# SurfaceEEG_Central_V1_0.net
KiCad netlist of a schematic drawn in EAGLE
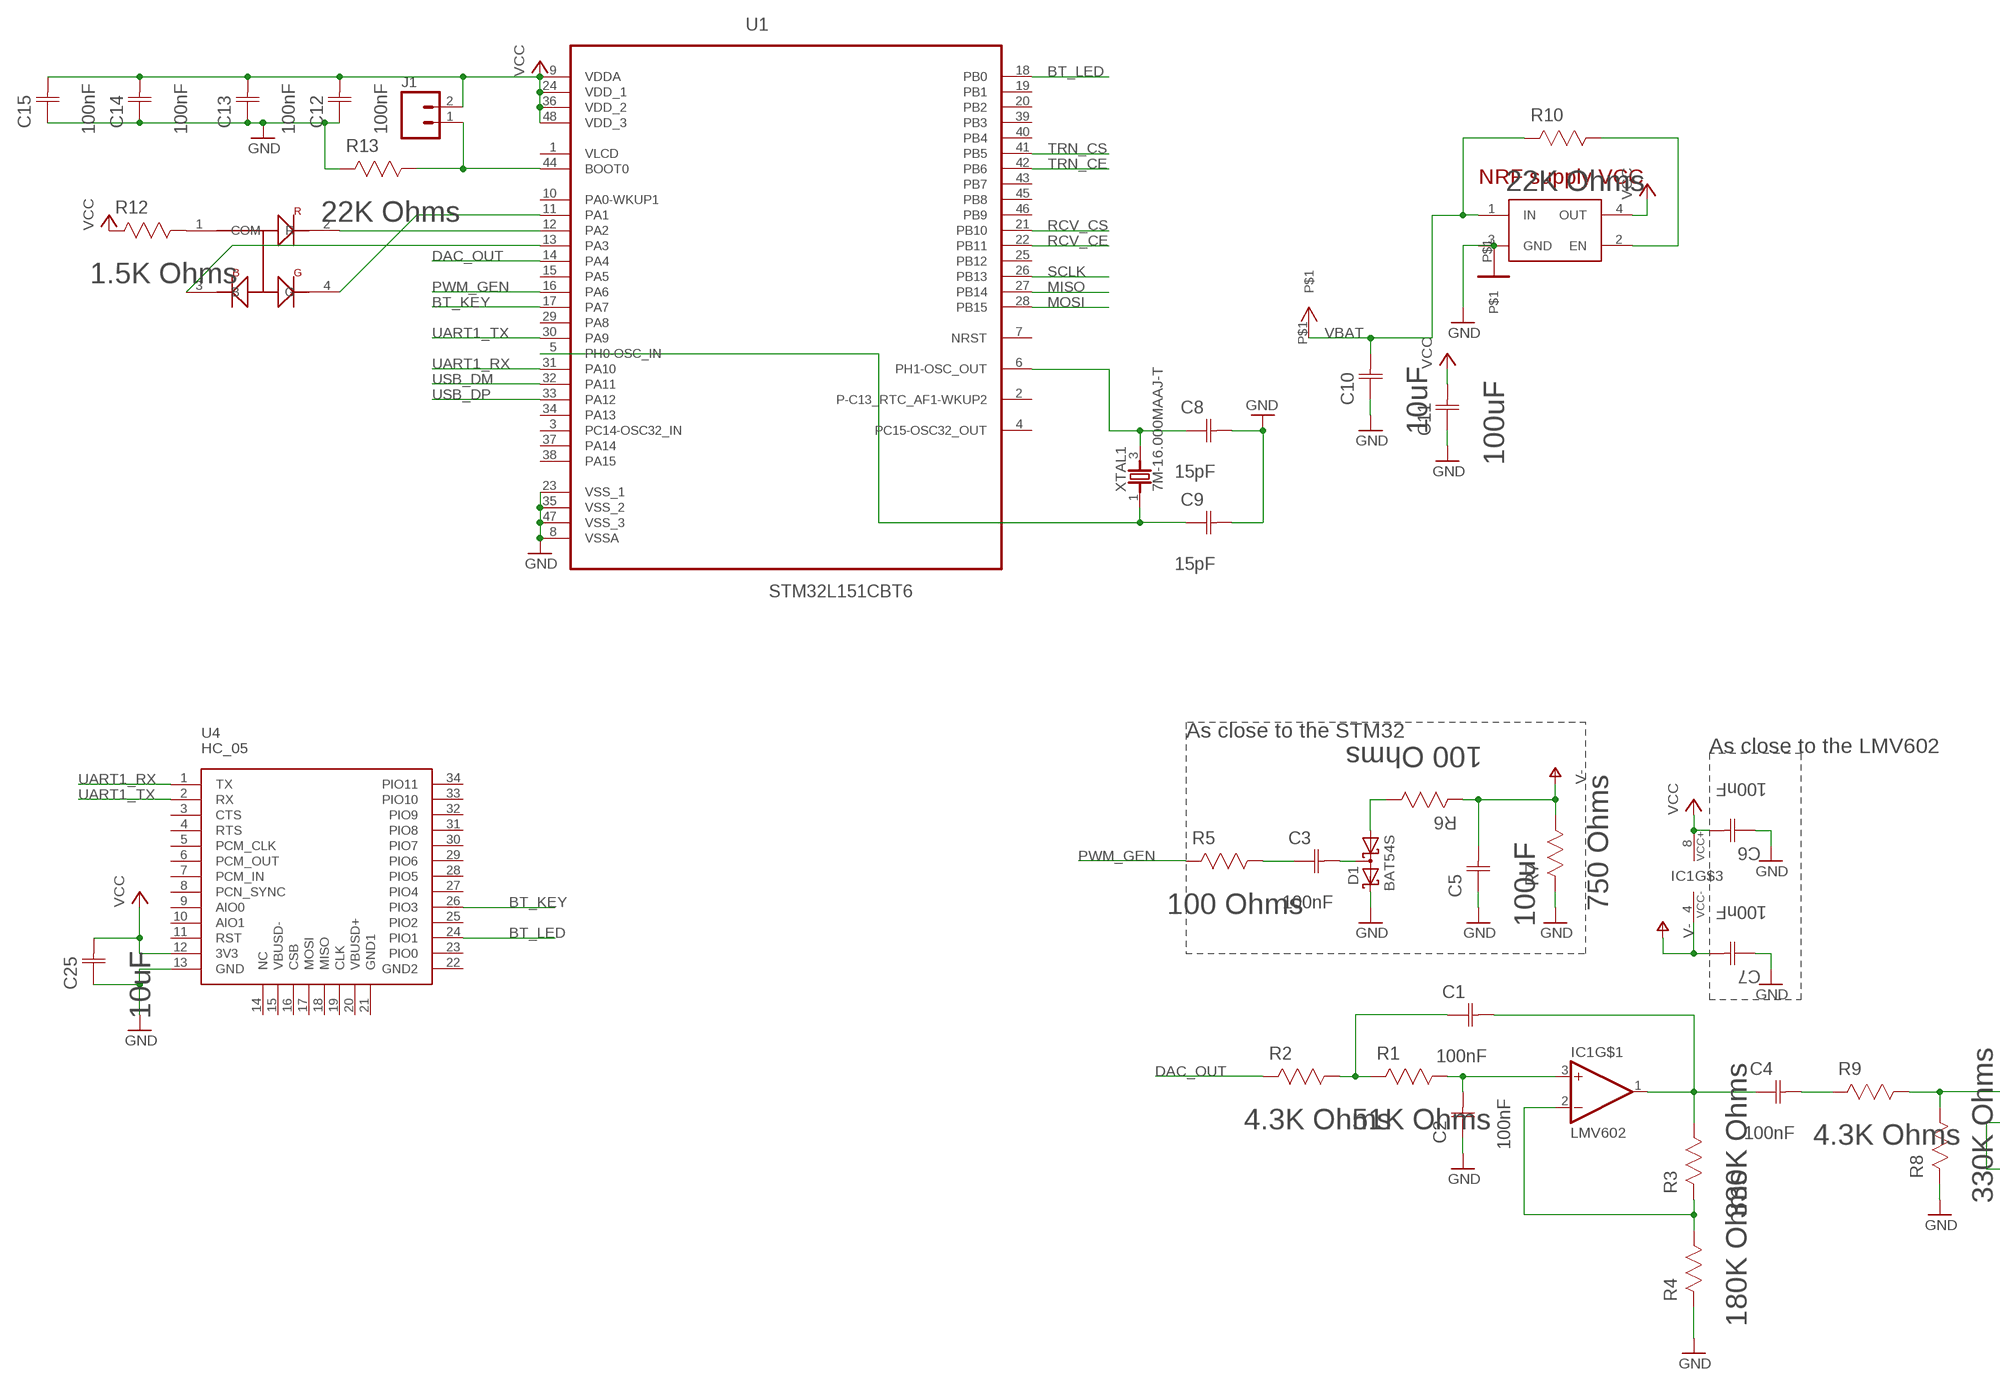
[diagram p0: schematic, sheet 1, part 1 of 2]
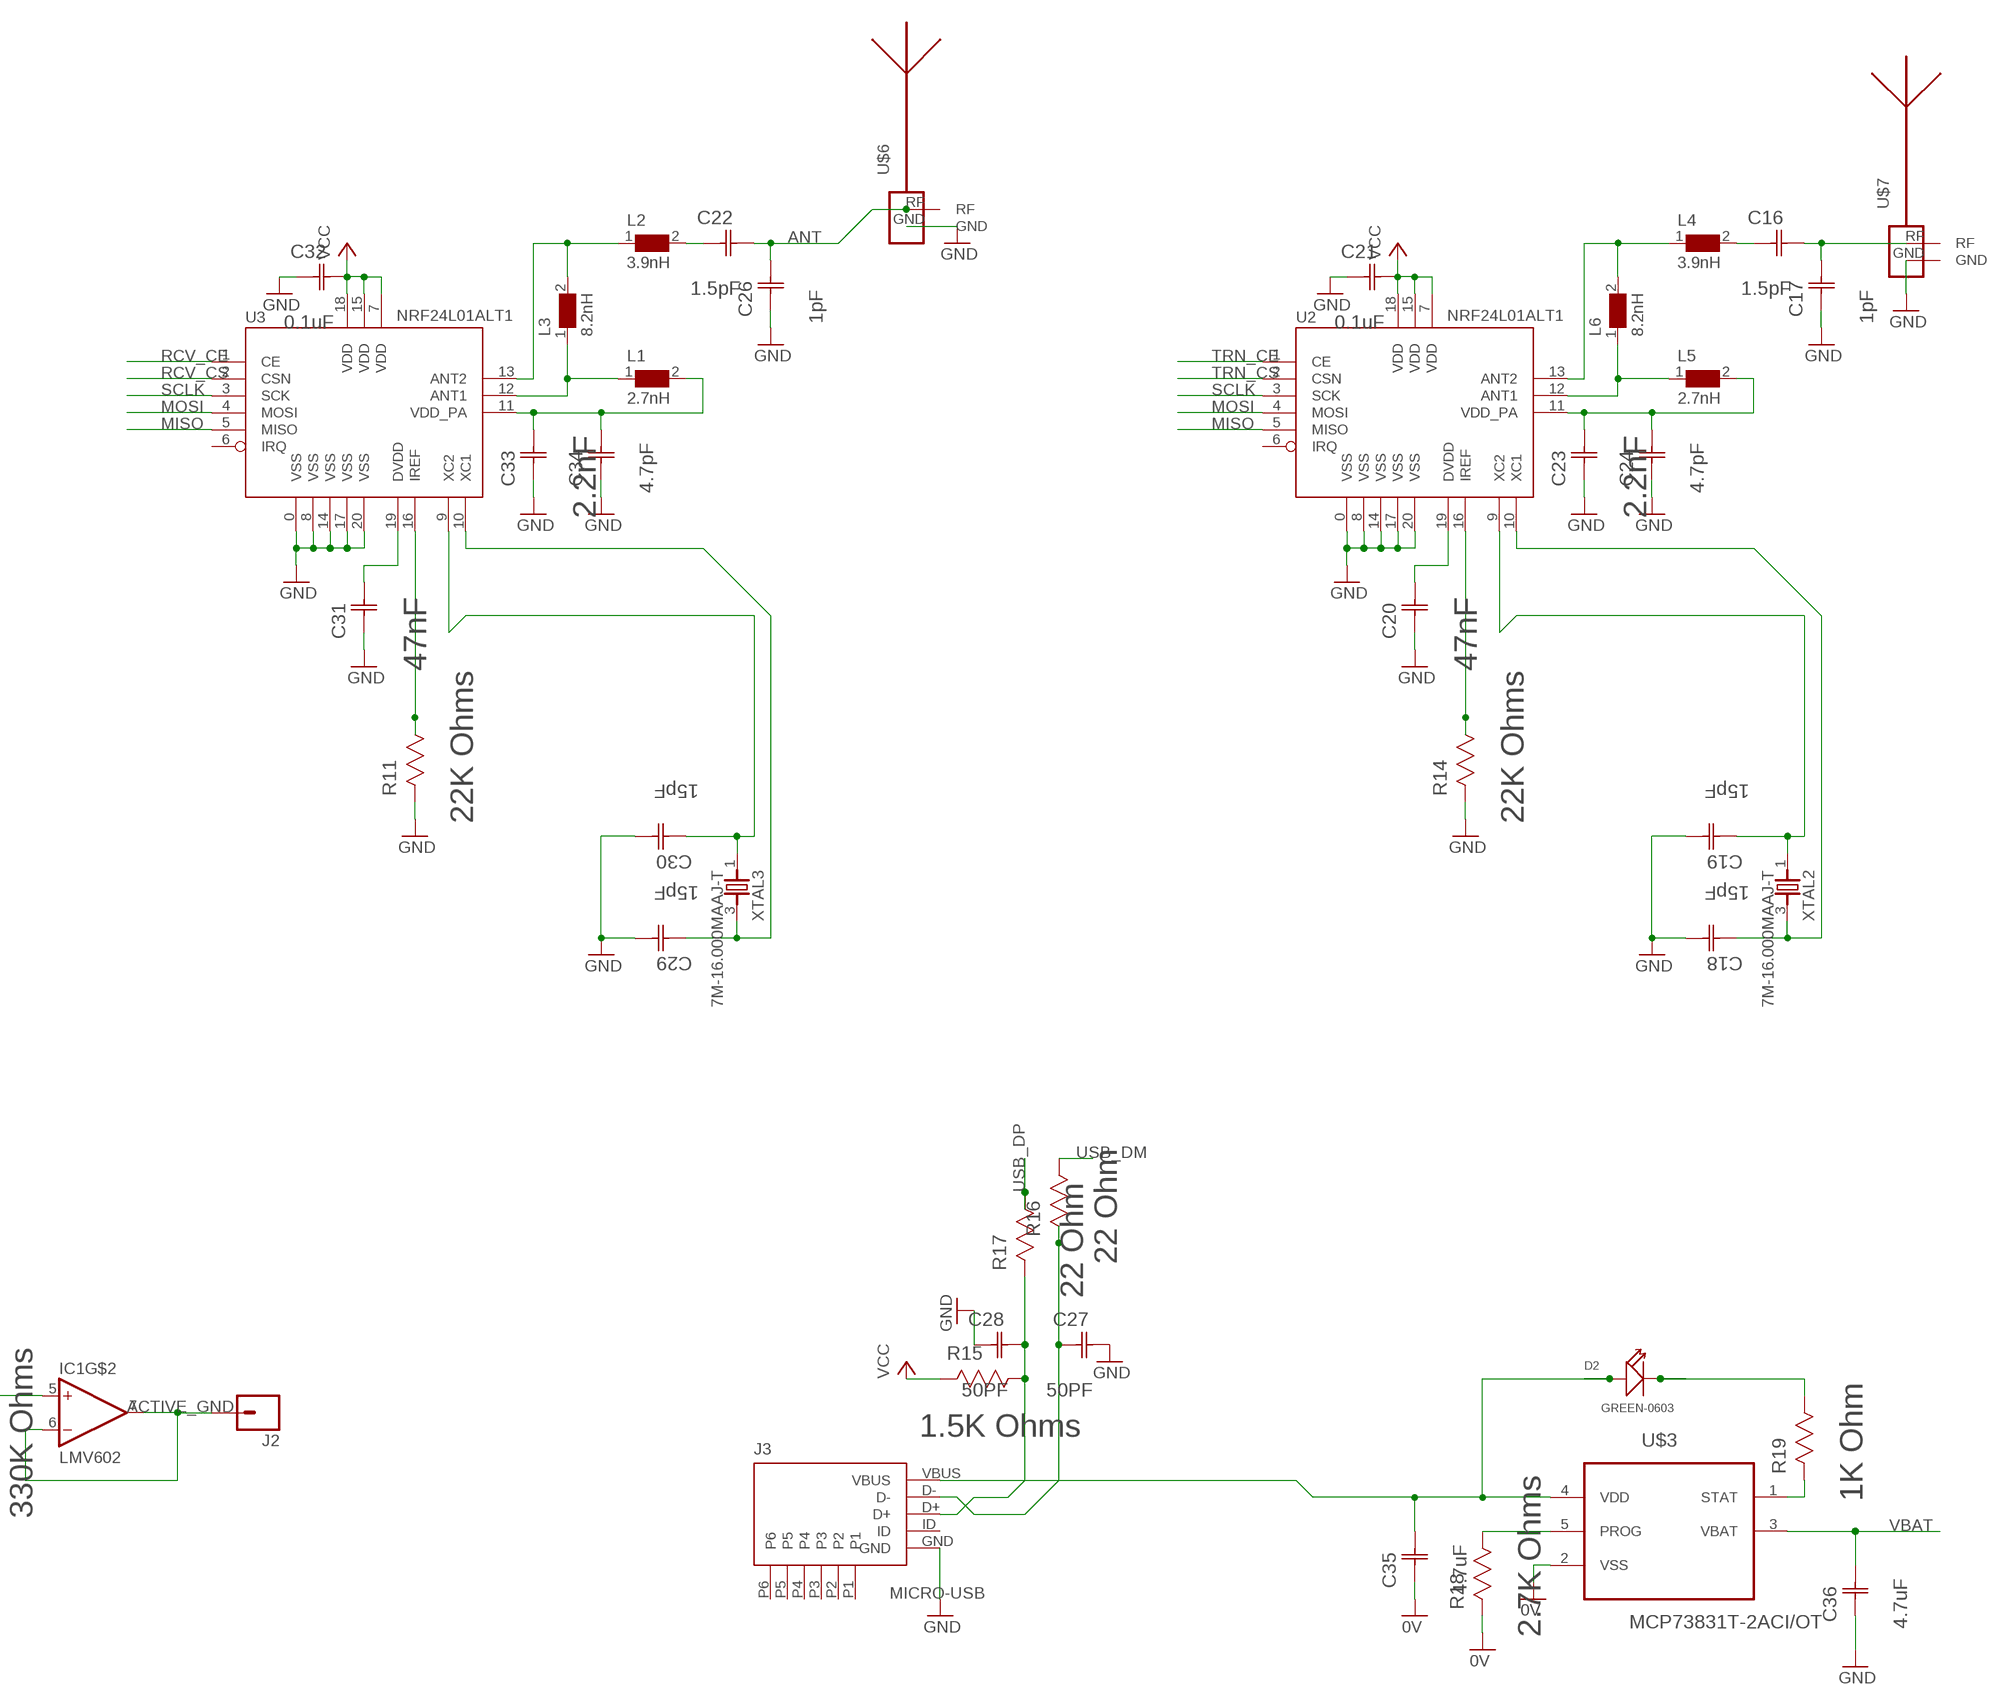
[diagram p1: schematic, sheet 1, part 2 of 2]

(export (version "E")
  (design (tool "Eeschema 10.0.6"))
  (components
    (comp (ref "C1")
      (value "100nF")
      (footprint "eagle-import:CAPC1608X90N")
      (fields (field (name "MPN") "06035C104KAT2A") (field (name "TOLERANCE") "±10%"))
      (libsource (lib "eagle-import") (part "06035C104KAT2A"))
    )
    (comp (ref "C2")
      (value "100nF")
      (footprint "eagle-import:CAPC1608X90N")
      (fields (field (name "MPN") "06035C104KAT2A") (field (name "TOLERANCE") "±10%"))
      (libsource (lib "eagle-import") (part "06035C104KAT2A"))
    )
    (comp (ref "C3")
      (value "100nF")
      (footprint "eagle-import:CAPC1608X90N")
      (fields (field (name "MPN") "06035C104KAT2A") (field (name "TOLERANCE") "±10%"))
      (libsource (lib "eagle-import") (part "06035C104KAT2A"))
    )
    (comp (ref "C4")
      (value "100nF")
      (footprint "eagle-import:CAPC1608X90N")
      (fields (field (name "MPN") "06035C104KAT2A") (field (name "TOLERANCE") "±10%"))
      (libsource (lib "eagle-import") (part "06035C104KAT2A"))
    )
    (comp (ref "C5")
      (value "100uF")
      (footprint "eagle-import:CAPC3216X180N")
      (fields (field (name "MPN") "C1206C107M9PACTU") (field (name "TOLERANCE") "±20%"))
      (libsource (lib "eagle-import") (part "C1206C107M9PACTU"))
    )
    (comp (ref "C6")
      (value "100nF")
      (footprint "eagle-import:CAPC1608X90N")
      (fields (field (name "MPN") "06035C104KAT2A") (field (name "TOLERANCE") "±10%"))
      (libsource (lib "eagle-import") (part "06035C104KAT2A"))
    )
    (comp (ref "C7")
      (value "100nF")
      (footprint "eagle-import:CAPC1608X90N")
      (fields (field (name "MPN") "06035C104KAT2A") (field (name "TOLERANCE") "±10%"))
      (libsource (lib "eagle-import") (part "06035C104KAT2A"))
    )
    (comp (ref "C8")
      (value "15pF")
      (footprint "eagle-import:CAPC1005X60N")
      (fields (field (name "MPN") "UQCL2A150JAT2A/500") (field (name "TOLERANCE") "±5%"))
      (libsource (lib "eagle-import") (part "UQCL2A150JAT2A/500"))
    )
    (comp (ref "C9")
      (value "15pF")
      (footprint "eagle-import:CAPC1005X60N")
      (fields (field (name "MPN") "UQCL2A150JAT2A/500") (field (name "TOLERANCE") "±5%"))
      (libsource (lib "eagle-import") (part "UQCL2A150JAT2A/500"))
    )
    (comp (ref "C10")
      (value "10uF")
      (footprint "eagle-import:CAPC1608X85N")
      (fields (field (name "MPN") "C0603C106M9PACTU") (field (name "TOLERANCE") "±20%"))
      (libsource (lib "eagle-import") (part "C0603C106M9PACTU"))
    )
    (comp (ref "C11")
      (value "100uF")
      (footprint "eagle-import:CAPC3216X180N")
      (fields (field (name "MPN") "C1206C107M9PACTU") (field (name "TOLERANCE") "±20%"))
      (libsource (lib "eagle-import") (part "C1206C107M9PACTU"))
    )
    (comp (ref "C12")
      (value "100nF")
      (footprint "eagle-import:CAPC1608X90N")
      (fields (field (name "MPN") "06035C104KAT2A") (field (name "TOLERANCE") "±10%"))
      (libsource (lib "eagle-import") (part "06035C104KAT2A"))
    )
    (comp (ref "C13")
      (value "100nF")
      (footprint "eagle-import:CAPC1608X90N")
      (fields (field (name "MPN") "06035C104KAT2A") (field (name "TOLERANCE") "±10%"))
      (libsource (lib "eagle-import") (part "06035C104KAT2A"))
    )
    (comp (ref "C14")
      (value "100nF")
      (footprint "eagle-import:CAPC1608X90N")
      (fields (field (name "MPN") "06035C104KAT2A") (field (name "TOLERANCE") "±10%"))
      (libsource (lib "eagle-import") (part "06035C104KAT2A"))
    )
    (comp (ref "C15")
      (value "100nF")
      (footprint "eagle-import:CAPC1608X90N")
      (fields (field (name "MPN") "06035C104KAT2A") (field (name "TOLERANCE") "±10%"))
      (libsource (lib "eagle-import") (part "06035C104KAT2A"))
    )
    (comp (ref "C16")
      (value "1.5pF")
      (footprint "eagle-import:CAPC1005X60N")
      (fields (field (name "MPN") "UQCL2A1R5BAT2A/500") (field (name "TOLERANCE") "±.1 pF"))
      (libsource (lib "eagle-import") (part "UQCL2A1R5BAT2A/500"))
    )
    (comp (ref "C17")
      (value "1pF")
      (footprint "eagle-import:CAPC1005X60N")
      (fields (field (name "MPN") "UQCL2A1R0BAT2A/500") (field (name "TOLERANCE") "±.1 pF"))
      (libsource (lib "eagle-import") (part "UQCL2A1R0BAT2A/500"))
    )
    (comp (ref "C18")
      (value "15pF")
      (footprint "eagle-import:CAPC1005X60N")
      (fields (field (name "MPN") "UQCL2A150JAT2A/500") (field (name "TOLERANCE") "±5%"))
      (libsource (lib "eagle-import") (part "UQCL2A150JAT2A/500"))
    )
    (comp (ref "C19")
      (value "15pF")
      (footprint "eagle-import:CAPC1005X60N")
      (fields (field (name "MPN") "UQCL2A150JAT2A/500") (field (name "TOLERANCE") "±5%"))
      (libsource (lib "eagle-import") (part "UQCL2A150JAT2A/500"))
    )
    (comp (ref "C20")
      (value "47nF")
      (footprint "eagle-import:CAPC1608X85N")
      (fields (field (name "MPN") "C0603C473K1RACTU") (field (name "TOLERANCE") "±10%"))
      (libsource (lib "eagle-import") (part "C0603C473K1RACTU"))
    )
    (comp (ref "C21")
      (value "0.1uF")
      (footprint "eagle-import:CAPC1005X60N")
      (fields (field (name "MPN") "04023C104KAT2A") (field (name "TOLERANCE") "±10%"))
      (libsource (lib "eagle-import") (part "04023C104KAT2A"))
    )
    (comp (ref "C22")
      (value "1.5pF")
      (footprint "eagle-import:CAPC1005X60N")
      (fields (field (name "MPN") "UQCL2A1R5BAT2A/500") (field (name "TOLERANCE") "±.1 pF"))
      (libsource (lib "eagle-import") (part "UQCL2A1R5BAT2A/500"))
    )
    (comp (ref "C23")
      (value "2.2nF")
      (footprint "eagle-import:CAPC1005X60N")
      (fields (field (name "MPN") "C0402C222K5RACTU") (field (name "TOLERANCE") "±10%"))
      (libsource (lib "eagle-import") (part "C0402C222K5RACTU"))
    )
    (comp (ref "C24")
      (value "4.7pF")
      (footprint "eagle-import:CAPC1005X60N")
      (fields (field (name "MPN") "UQCL2A4R7CAT2A/500") (field (name "TOLERANCE") "±.25 pF"))
      (libsource (lib "eagle-import") (part "UQCL2A4R7CAT2A/500"))
    )
    (comp (ref "C25")
      (value "10uF")
      (footprint "eagle-import:CAPC1608X85N")
      (fields (field (name "MPN") "C0603C106M9PACTU") (field (name "TOLERANCE") "±20%"))
      (libsource (lib "eagle-import") (part "C0603C106M9PACTU"))
    )
    (comp (ref "C26")
      (value "1pF")
      (footprint "eagle-import:CAPC1005X60N")
      (fields (field (name "MPN") "UQCL2A1R0BAT2A/500") (field (name "TOLERANCE") "±.1 pF"))
      (libsource (lib "eagle-import") (part "UQCL2A1R0BAT2A/500"))
    )
    (comp (ref "C27")
      (value "50PF")
      (footprint "eagle-import:CAPC1608X90N")
      (fields (field (name "MPN") "06035A500JAT2A") (field (name "TOLERANCE") "±5%"))
      (libsource (lib "eagle-import") (part "06035A500JAT2A"))
    )
    (comp (ref "C28")
      (value "50PF")
      (footprint "eagle-import:CAPC1608X90N")
      (fields (field (name "MPN") "06035A500JAT2A") (field (name "TOLERANCE") "±5%"))
      (libsource (lib "eagle-import") (part "06035A500JAT2A"))
    )
    (comp (ref "C29")
      (value "15pF")
      (footprint "eagle-import:CAPC1005X60N")
      (fields (field (name "MPN") "UQCL2A150JAT2A/500") (field (name "TOLERANCE") "±5%"))
      (libsource (lib "eagle-import") (part "UQCL2A150JAT2A/500"))
    )
    (comp (ref "C30")
      (value "15pF")
      (footprint "eagle-import:CAPC1005X60N")
      (fields (field (name "MPN") "UQCL2A150JAT2A/500") (field (name "TOLERANCE") "±5%"))
      (libsource (lib "eagle-import") (part "UQCL2A150JAT2A/500"))
    )
    (comp (ref "C31")
      (value "47nF")
      (footprint "eagle-import:CAPC1608X85N")
      (fields (field (name "MPN") "C0603C473K1RACTU") (field (name "TOLERANCE") "±10%"))
      (libsource (lib "eagle-import") (part "C0603C473K1RACTU"))
    )
    (comp (ref "C32")
      (value "0.1uF")
      (footprint "eagle-import:CAPC1005X60N")
      (fields (field (name "MPN") "04023C104KAT2A") (field (name "TOLERANCE") "±10%"))
      (libsource (lib "eagle-import") (part "04023C104KAT2A"))
    )
    (comp (ref "C33")
      (value "2.2nF")
      (footprint "eagle-import:CAPC1005X60N")
      (fields (field (name "MPN") "C0402C222K5RACTU") (field (name "TOLERANCE") "±10%"))
      (libsource (lib "eagle-import") (part "C0402C222K5RACTU"))
    )
    (comp (ref "C34")
      (value "4.7pF")
      (footprint "eagle-import:CAPC1005X60N")
      (fields (field (name "MPN") "UQCL2A4R7CAT2A/500") (field (name "TOLERANCE") "±.25 pF"))
      (libsource (lib "eagle-import") (part "UQCL2A4R7CAT2A/500"))
    )
    (comp (ref "C35")
      (value "4.7uF")
      (footprint "eagle-import:CAPC2013X152N")
      (fields (field (name "MPN") "0805YC475KAT2A") (field (name "TOLERANCE") "±10%"))
      (libsource (lib "eagle-import") (part "0805YC475KAT2A"))
    )
    (comp (ref "C36")
      (value "4.7uF")
      (footprint "eagle-import:CAPC2013X152N")
      (fields (field (name "MPN") "0805YC475KAT2A") (field (name "TOLERANCE") "±10%"))
      (libsource (lib "eagle-import") (part "0805YC475KAT2A"))
    )
    (comp (ref "D1")
      (value "BAT54S")
      (footprint "eagle-import:SOT23")
      (libsource (lib "eagle-import") (part "BAT54S"))
    )
    (comp (ref "D2")
      (value "GREEN-0603")
      (footprint "eagle-import:LED-0603")
      (fields (field (name "MPN") "19-217-G7C-AN1P2-3T"))
      (libsource (lib "eagle-import") (part "SMD-LED-CLEAR-GREEN(0603)"))
    )
    (comp (ref "IC1")
      (value "LMV602")
      (footprint "eagle-import:VSSOP8")
      (fields (field (name "MPN") "LMV602MM/NOPB"))
      (libsource (lib "eagle-import") (part "LMV602"))
    )
    (comp (ref "J1")
      (value "M02PTH")
      (footprint "eagle-import:1X02")
      (libsource (lib "eagle-import") (part "M02PTH"))
    )
    (comp (ref "J2")
      (value "M01SMD-4.5X1.5")
      (footprint "eagle-import:PAD-1.5X4.5")
      (libsource (lib "eagle-import") (part "M01SMD-4.5X1.5"))
    )
    (comp (ref "J3")
      (value "MICRO-USB")
      (footprint "eagle-import:MICRO_USB")
      (fields (field (name "MPN") "47346-0001") (field (name "PARTNO") "AS-ITM-00021"))
      (libsource (lib "eagle-import") (part "MICRO-USB"))
    )
    (comp (ref "L1")
      (value "2.7nH")
      (footprint "eagle-import:WE-KI_0402A")
      (fields (field (name "MPN") "744765027A"))
      (libsource (lib "eagle-import") (part "WE-KI_0402A-744765027A"))
    )
    (comp (ref "L2")
      (value "3.9nH")
      (footprint "eagle-import:WE-KI_0402A")
      (fields (field (name "MPN") "744765039A"))
      (libsource (lib "eagle-import") (part "WE-KI_0402A-744765039A"))
    )
    (comp (ref "L3")
      (value "8.2nH")
      (footprint "eagle-import:WE-KI_0402A")
      (fields (field (name "MPN") "744765082A"))
      (libsource (lib "eagle-import") (part "WE-KI_0402A-744765082A"))
    )
    (comp (ref "L4")
      (value "3.9nH")
      (footprint "eagle-import:WE-KI_0402A")
      (fields (field (name "MPN") "744765039A"))
      (libsource (lib "eagle-import") (part "WE-KI_0402A-744765039A"))
    )
    (comp (ref "L5")
      (value "2.7nH")
      (footprint "eagle-import:WE-KI_0402A")
      (fields (field (name "MPN") "744765027A"))
      (libsource (lib "eagle-import") (part "WE-KI_0402A-744765027A"))
    )
    (comp (ref "L6")
      (value "8.2nH")
      (footprint "eagle-import:WE-KI_0402A")
      (fields (field (name "MPN") "744765082A"))
      (libsource (lib "eagle-import") (part "WE-KI_0402A-744765082A"))
    )
    (comp (ref "R1")
      (value "51K Ohms")
      (footprint "eagle-import:RESC1608X60N")
      (fields (field (name "MPN") "RC0603FR-0751KL") (field (name "TOLERANCE") "±1%"))
      (libsource (lib "eagle-import") (part "RC0603FR-0751KL"))
    )
    (comp (ref "R2")
      (value "4.3K Ohms")
      (footprint "eagle-import:RESC1608X60N")
      (fields (field (name "MPN") "RC0603FR-074K3L") (field (name "TOLERANCE") "±1%"))
      (libsource (lib "eagle-import") (part "RC0603FR-074K3L"))
    )
    (comp (ref "R3")
      (value "330K Ohms")
      (footprint "eagle-import:RESC1608X60N")
      (fields (field (name "MPN") "RC0603JR-07330KL") (field (name "TOLERANCE") "±5%"))
      (libsource (lib "eagle-import") (part "RC0603JR-07330KL"))
    )
    (comp (ref "R4")
      (value "180K Ohms")
      (footprint "eagle-import:RESC1608X60N")
      (fields (field (name "MPN") "RC0603JR-07180KL") (field (name "TOLERANCE") "±5%"))
      (libsource (lib "eagle-import") (part "RC0603JR-07180KL"))
    )
    (comp (ref "R5")
      (value "100 Ohms")
      (footprint "eagle-import:RESC1608X60N")
      (fields (field (name "MPN") "RC0603FR-07100RL") (field (name "TOLERANCE") "±1%"))
      (libsource (lib "eagle-import") (part "RC0603FR-07100RL"))
    )
    (comp (ref "R6")
      (value "100 Ohms")
      (footprint "eagle-import:RESC1608X60N")
      (fields (field (name "MPN") "RC0603FR-07100RL") (field (name "TOLERANCE") "±1%"))
      (libsource (lib "eagle-import") (part "RC0603FR-07100RL"))
    )
    (comp (ref "R7")
      (value "750 Ohms")
      (footprint "eagle-import:RESC1608X60N")
      (fields (field (name "MPN") "RC0603FR-07750RL") (field (name "TOLERANCE") "±1%"))
      (libsource (lib "eagle-import") (part "RC0603FR-07750RL"))
    )
    (comp (ref "R8")
      (value "330K Ohms")
      (footprint "eagle-import:RESC1608X60N")
      (fields (field (name "MPN") "RC0603JR-07330KL") (field (name "TOLERANCE") "±5%"))
      (libsource (lib "eagle-import") (part "RC0603JR-07330KL"))
    )
    (comp (ref "R9")
      (value "4.3K Ohms")
      (footprint "eagle-import:RESC1608X60N")
      (fields (field (name "MPN") "RC0603FR-074K3L") (field (name "TOLERANCE") "±1%"))
      (libsource (lib "eagle-import") (part "RC0603FR-074K3L"))
    )
    (comp (ref "R10")
      (value "22K Ohms")
      (footprint "eagle-import:RESC1608X60N")
      (fields (field (name "MPN") "RC0603FR-0722KL") (field (name "TOLERANCE") "±1%"))
      (libsource (lib "eagle-import") (part "RC0603FR-0722KL"))
    )
    (comp (ref "R11")
      (value "22K Ohms")
      (footprint "eagle-import:RESC1608X60N")
      (fields (field (name "MPN") "RC0603FR-0722KL") (field (name "TOLERANCE") "±1%"))
      (libsource (lib "eagle-import") (part "RC0603FR-0722KL"))
    )
    (comp (ref "R12")
      (value "1.5K Ohms")
      (footprint "eagle-import:RESC1608X60N")
      (fields (field (name "MPN") "RC0603FR-071K5L") (field (name "TOLERANCE") "±1%"))
      (libsource (lib "eagle-import") (part "RC0603FR-071K5L"))
    )
    (comp (ref "R13")
      (value "22K Ohms")
      (footprint "eagle-import:RESC1608X60N")
      (fields (field (name "MPN") "RC0603FR-0722KL") (field (name "TOLERANCE") "±1%"))
      (libsource (lib "eagle-import") (part "RC0603FR-0722KL"))
    )
    (comp (ref "R14")
      (value "22K Ohms")
      (footprint "eagle-import:RESC1608X60N")
      (fields (field (name "MPN") "RC0603FR-0722KL") (field (name "TOLERANCE") "±1%"))
      (libsource (lib "eagle-import") (part "RC0603FR-0722KL"))
    )
    (comp (ref "R15")
      (value "1.5K Ohms")
      (footprint "eagle-import:RESC1608X60N")
      (fields (field (name "MPN") "RC0603FR-071K5L") (field (name "TOLERANCE") "±1%"))
      (libsource (lib "eagle-import") (part "RC0603FR-071K5L"))
    )
    (comp (ref "R16")
      (value "22 Ohm")
      (footprint "eagle-import:RESC1608X60N")
      (fields (field (name "MPN") "9C06031A22R0JLHFT") (field (name "TOLERANCE") "±5%"))
      (libsource (lib "eagle-import") (part "9C06031A22R0JLHFT"))
    )
    (comp (ref "R17")
      (value "22 Ohm")
      (footprint "eagle-import:RESC1608X60N")
      (fields (field (name "MPN") "9C06031A22R0JLHFT") (field (name "TOLERANCE") "±5%"))
      (libsource (lib "eagle-import") (part "9C06031A22R0JLHFT"))
    )
    (comp (ref "R18")
      (value "2.7K Ohms")
      (footprint "eagle-import:RESC1608X60N")
      (fields (field (name "MPN") "RC0603FR-072K7L") (field (name "TOLERANCE") "±1%"))
      (libsource (lib "eagle-import") (part "RC0603FR-072K7L"))
    )
    (comp (ref "R19")
      (value "1K Ohm")
      (footprint "eagle-import:RESC1608X60N")
      (fields (field (name "MPN") "9C06031A1001JLHFT") (field (name "TOLERANCE") "±5%"))
      (libsource (lib "eagle-import") (part "9C06031A1001JLHFT"))
    )
    (comp (ref "U$1")
      (value "NCP103")
      (footprint "eagle-import:UDFN4-1_1")
      (fields (field (name "MPN") "NCP103AMX330TCG"))
      (libsource (lib "eagle-import") (part "NCP103"))
    )
    (comp (ref "U$2")
      (value "RGB-LED")
      (footprint "eagle-import:1615-RGB-LED")
      (libsource (lib "eagle-import") (part "RGB-LED"))
    )
    (comp (ref "U$3")
      (value "MCP73831T-2ACI/OT")
      (footprint "eagle-import:SOT95P280X145-5N")
      (libsource (lib "eagle-import") (part "MCP73831T-2ACI/OT"))
    )
    (comp (ref "U$4")
      (value "VCC")
      (footprint "eagle-import:VCC-PAD")
      (libsource (lib "eagle-import") (part "VCC"))
    )
    (comp (ref "U$5")
      (value "GND")
      (footprint "eagle-import:GND-PAD")
      (libsource (lib "eagle-import") (part "GND"))
    )
    (comp (ref "U$6")
      (value "ANTENNA_1LEFT")
      (footprint "eagle-import:SWRA117D_LEFT")
      (libsource (lib "eagle-import") (part "ANTENNA_1LEFT"))
    )
    (comp (ref "U$7")
      (value "ANTENNA_1RIGHT")
      (footprint "eagle-import:SWRA117D_RIGHT")
      (libsource (lib "eagle-import") (part "ANTENNA_1RIGHT"))
    )
    (comp (ref "U1")
      (value "STM32L151CBT6")
      (footprint "eagle-import:QFP50P900X900X160-48N")
      (libsource (lib "eagle-import") (part "STM32L151CBT6"))
    )
    (comp (ref "U2")
      (value "NRF24L01ALT1")
      (footprint "eagle-import:QFN20_ALT1")
      (libsource (lib "eagle-import") (part "NRF24L01ALT1"))
    )
    (comp (ref "U3")
      (value "NRF24L01ALT1")
      (footprint "eagle-import:QFN20_ALT1")
      (libsource (lib "eagle-import") (part "NRF24L01ALT1"))
    )
    (comp (ref "U4")
      (value "HC_05")
      (footprint "eagle-import:BLUETOOTH_SMD")
      (libsource (lib "eagle-import") (part "HC_05"))
    )
    (comp (ref "XTAL1")
      (value "7M-16.000MAAJ-T")
      (footprint "eagle-import:TXC_7M-16.000MAAJ-T")
      (fields (field (name "MPN") "7M-16.000MAAJ-T "))
      (libsource (lib "eagle-import") (part "7M-16.000MAAJ-T"))
    )
    (comp (ref "XTAL2")
      (value "7M-16.000MAAJ-T")
      (footprint "eagle-import:TXC_7M-16.000MAAJ-T")
      (fields (field (name "MPN") "7M-16.000MAAJ-T "))
      (libsource (lib "eagle-import") (part "7M-16.000MAAJ-T"))
    )
    (comp (ref "XTAL3")
      (value "7M-16.000MAAJ-T")
      (footprint "eagle-import:TXC_7M-16.000MAAJ-T")
      (fields (field (name "MPN") "7M-16.000MAAJ-T "))
      (libsource (lib "eagle-import") (part "7M-16.000MAAJ-T"))
    )
  )
  (nets
    (net (code "1") (name "/ACTIVE_GND") (class "Default")
      (node (ref "IC1") (pin "6") (pinfunction "IN-_6") (pintype "input"))
      (node (ref "IC1") (pin "7") (pinfunction "OUT_7") (pintype "output"))
      (node (ref "J2") (pin "P$1") (pinfunction "1_P$1") (pintype "passive"))
    )
    (net (code "2") (name "/ANT") (class "Default")
      (node (ref "C22") (pin "1") (pinfunction "C2_1") (pintype "passive"))
      (node (ref "C26") (pin "1") (pinfunction "C2_1") (pintype "passive"))
      (node (ref "U$6") (pin "RF") (pinfunction "RF_RF") (pintype "bidirectional"))
    )
    (net (code "3") (name "/BT_KEY") (class "Default")
      (node (ref "U1") (pin "17") (pinfunction "PA7_17") (pintype "bidirectional"))
      (node (ref "U4") (pin "26") (pinfunction "PIO3_26") (pintype "bidirectional"))
    )
    (net (code "4") (name "/BT_LED") (class "Default")
      (node (ref "U1") (pin "18") (pinfunction "PB0_18") (pintype "bidirectional"))
      (node (ref "U4") (pin "24") (pinfunction "PIO1_24") (pintype "bidirectional"))
    )
    (net (code "5") (name "/DAC_OUT") (class "Default")
      (node (ref "R2") (pin "2") (pinfunction "R2_2") (pintype "passive"))
      (node (ref "U1") (pin "14") (pinfunction "PA4_14") (pintype "bidirectional"))
    )
    (net (code "6") (name "/MISO") (class "Default")
      (node (ref "U1") (pin "27") (pinfunction "PB14_27") (pintype "bidirectional"))
      (node (ref "U2") (pin "5") (pinfunction "MISO_5") (pintype "output"))
      (node (ref "U3") (pin "5") (pinfunction "MISO_5") (pintype "output"))
    )
    (net (code "7") (name "/MOSI") (class "Default")
      (node (ref "U1") (pin "28") (pinfunction "PB15_28") (pintype "bidirectional"))
      (node (ref "U2") (pin "4") (pinfunction "MOSI_4") (pintype "input"))
      (node (ref "U3") (pin "4") (pinfunction "MOSI_4") (pintype "input"))
    )
    (net (code "8") (name "/PWM_GEN") (class "Default")
      (node (ref "R5") (pin "2") (pinfunction "R2_2") (pintype "passive"))
      (node (ref "U1") (pin "16") (pinfunction "PA6_16") (pintype "bidirectional"))
    )
    (net (code "9") (name "/RCV_CE") (class "Default")
      (node (ref "U1") (pin "22") (pinfunction "PB11_22") (pintype "bidirectional"))
      (node (ref "U3") (pin "1") (pinfunction "CE_1") (pintype "input"))
    )
    (net (code "10") (name "/RCV_CS") (class "Default")
      (node (ref "U1") (pin "21") (pinfunction "PB10_21") (pintype "bidirectional"))
      (node (ref "U3") (pin "2") (pinfunction "CSN_2") (pintype "input"))
    )
    (net (code "11") (name "/SCLK") (class "Default")
      (node (ref "U1") (pin "26") (pinfunction "PB13_26") (pintype "bidirectional"))
      (node (ref "U2") (pin "3") (pinfunction "SCK_3") (pintype "input"))
      (node (ref "U3") (pin "3") (pinfunction "SCK_3") (pintype "input"))
    )
    (net (code "12") (name "/TRN_CE") (class "Default")
      (node (ref "U1") (pin "42") (pinfunction "PB6_42") (pintype "bidirectional"))
      (node (ref "U2") (pin "1") (pinfunction "CE_1") (pintype "input"))
    )
    (net (code "13") (name "/TRN_CS") (class "Default")
      (node (ref "U1") (pin "41") (pinfunction "PB5_41") (pintype "bidirectional"))
      (node (ref "U2") (pin "2") (pinfunction "CSN_2") (pintype "input"))
    )
    (net (code "14") (name "/UART1_RX") (class "Default")
      (node (ref "U1") (pin "31") (pinfunction "PA10_31") (pintype "bidirectional"))
      (node (ref "U4") (pin "1") (pinfunction "TX_1") (pintype "bidirectional"))
    )
    (net (code "15") (name "/UART1_TX") (class "Default")
      (node (ref "U1") (pin "30") (pinfunction "PA9_30") (pintype "bidirectional"))
      (node (ref "U4") (pin "2") (pinfunction "RX_2") (pintype "bidirectional"))
    )
    (net (code "16") (name "/USB_DM") (class "Default")
      (node (ref "R16") (pin "1") (pinfunction "R1_1") (pintype "passive"))
      (node (ref "U1") (pin "32") (pinfunction "PA11_32") (pintype "bidirectional"))
    )
    (net (code "17") (name "/USB_DP") (class "Default")
      (node (ref "R17") (pin "1") (pinfunction "R1_1") (pintype "passive"))
      (node (ref "U1") (pin "33") (pinfunction "PA12_33") (pintype "bidirectional"))
    )
    (net (code "18") (name "/VBAT") (class "Default")
      (node (ref "C10") (pin "2") (pinfunction "C2_2") (pintype "passive"))
      (node (ref "C36") (pin "2") (pinfunction "C2_2") (pintype "passive"))
      (node (ref "R10") (pin "2") (pinfunction "R2_2") (pintype "passive"))
      (node (ref "U$1") (pin "1") (pinfunction "IN_1") (pintype "bidirectional"))
      (node (ref "U$3") (pin "3") (pinfunction "VBAT_3") (pintype "output"))
      (node (ref "U$4") (pin "P$1") (pinfunction "P$1_P$1") (pintype "bidirectional"))
    )
    (net (code "19") (name "/VLCD") (class "Default")
      (node (ref "U1") (pin "1") (pinfunction "VLCD_1") (pintype "power_in"))
    )
    (net (code "20") (name "0V") (class "Default")
      (node (ref "C35") (pin "1") (pinfunction "C1_1") (pintype "passive"))
      (node (ref "R18") (pin "2") (pinfunction "R2_2") (pintype "passive"))
      (node (ref "U$3") (pin "2") (pinfunction "VSS_2") (pintype "power_in"))
    )
    (net (code "21") (name "GND") (class "Default")
      (node (ref "C10") (pin "1") (pinfunction "C1_1") (pintype "passive"))
      (node (ref "C11") (pin "1") (pinfunction "C1_1") (pintype "passive"))
      (node (ref "C12") (pin "1") (pinfunction "C1_1") (pintype "passive"))
      (node (ref "C13") (pin "1") (pinfunction "C1_1") (pintype "passive"))
      (node (ref "C14") (pin "1") (pinfunction "C1_1") (pintype "passive"))
      (node (ref "C15") (pin "1") (pinfunction "C1_1") (pintype "passive"))
      (node (ref "C17") (pin "2") (pinfunction "C1_2") (pintype "passive"))
      (node (ref "C18") (pin "1") (pinfunction "C2_1") (pintype "passive"))
      (node (ref "C19") (pin "1") (pinfunction "C2_1") (pintype "passive"))
      (node (ref "C2") (pin "1") (pinfunction "C1_1") (pintype "passive"))
      (node (ref "C20") (pin "1") (pinfunction "C1_1") (pintype "passive"))
      (node (ref "C21") (pin "2") (pinfunction "C1_2") (pintype "passive"))
      (node (ref "C23") (pin "1") (pinfunction "C1_1") (pintype "passive"))
      (node (ref "C24") (pin "2") (pinfunction "C1_2") (pintype "passive"))
      (node (ref "C25") (pin "1") (pinfunction "C1_1") (pintype "passive"))
      (node (ref "C26") (pin "2") (pinfunction "C1_2") (pintype "passive"))
      (node (ref "C27") (pin "2") (pinfunction "C2_2") (pintype "passive"))
      (node (ref "C28") (pin "1") (pinfunction "C1_1") (pintype "passive"))
      (node (ref "C29") (pin "1") (pinfunction "C2_1") (pintype "passive"))
      (node (ref "C30") (pin "1") (pinfunction "C2_1") (pintype "passive"))
      (node (ref "C31") (pin "1") (pinfunction "C1_1") (pintype "passive"))
      (node (ref "C32") (pin "2") (pinfunction "C1_2") (pintype "passive"))
      (node (ref "C33") (pin "1") (pinfunction "C1_1") (pintype "passive"))
      (node (ref "C34") (pin "2") (pinfunction "C1_2") (pintype "passive"))
      (node (ref "C36") (pin "1") (pinfunction "C1_1") (pintype "passive"))
      (node (ref "C5") (pin "1") (pinfunction "C1_1") (pintype "passive"))
      (node (ref "C6") (pin "1") (pinfunction "C1_1") (pintype "passive"))
      (node (ref "C7") (pin "1") (pinfunction "C1_1") (pintype "passive"))
      (node (ref "C8") (pin "1") (pinfunction "C2_1") (pintype "passive"))
      (node (ref "C9") (pin "1") (pinfunction "C2_1") (pintype "passive"))
      (node (ref "D1") (pin "2") (pinfunction "C2_2") (pintype "passive"))
      (node (ref "J3") (pin "GND") (pinfunction "GND_GND") (pintype "bidirectional"))
      (node (ref "R11") (pin "2") (pinfunction "R2_2") (pintype "passive"))
      (node (ref "R13") (pin "2") (pinfunction "R2_2") (pintype "passive"))
      (node (ref "R14") (pin "2") (pinfunction "R2_2") (pintype "passive"))
      (node (ref "R4") (pin "2") (pinfunction "R2_2") (pintype "passive"))
      (node (ref "R7") (pin "2") (pinfunction "R2_2") (pintype "passive"))
      (node (ref "R8") (pin "2") (pinfunction "R2_2") (pintype "passive"))
      (node (ref "U$1") (pin "3") (pinfunction "GND_3") (pintype "bidirectional"))
      (node (ref "U$5") (pin "P$1") (pinfunction "P$1_P$1") (pintype "bidirectional"))
      (node (ref "U$6") (pin "GND") (pinfunction "GND_GND") (pintype "passive"))
      (node (ref "U$7") (pin "GND") (pinfunction "GND_GND") (pintype "passive"))
      (node (ref "U1") (pin "23") (pinfunction "VSS_1_23") (pintype "power_in"))
      (node (ref "U1") (pin "35") (pinfunction "VSS_2_35") (pintype "power_in"))
      (node (ref "U1") (pin "47") (pinfunction "VSS_3_47") (pintype "power_in"))
      (node (ref "U1") (pin "8") (pinfunction "VSSA_8") (pintype "power_in"))
      (node (ref "U2") (pin "0") (pinfunction "VSS_0") (pintype "power_in"))
      (node (ref "U2") (pin "14") (pinfunction "VSS_14") (pintype "power_in"))
      (node (ref "U2") (pin "17") (pinfunction "VSS_17") (pintype "power_in"))
      (node (ref "U2") (pin "20") (pinfunction "VSS_20") (pintype "power_in"))
      (node (ref "U2") (pin "8") (pinfunction "VSS_8") (pintype "power_in"))
      (node (ref "U3") (pin "0") (pinfunction "VSS_0") (pintype "power_in"))
      (node (ref "U3") (pin "14") (pinfunction "VSS_14") (pintype "power_in"))
      (node (ref "U3") (pin "17") (pinfunction "VSS_17") (pintype "power_in"))
      (node (ref "U3") (pin "20") (pinfunction "VSS_20") (pintype "power_in"))
      (node (ref "U3") (pin "8") (pinfunction "VSS_8") (pintype "power_in"))
      (node (ref "U4") (pin "13") (pinfunction "GND_13") (pintype "bidirectional"))
    )
    (net (code "22") (name "Net-(C1-C1)") (class "Default")
      (node (ref "C1") (pin "1") (pinfunction "C1_1") (pintype "passive"))
      (node (ref "R1") (pin "2") (pinfunction "R2_2") (pintype "passive"))
      (node (ref "R2") (pin "1") (pinfunction "R1_1") (pintype "passive"))
    )
    (net (code "23") (name "Net-(C1-C2)") (class "Default")
      (node (ref "C1") (pin "2") (pinfunction "C2_2") (pintype "passive"))
      (node (ref "C4") (pin "1") (pinfunction "C1_1") (pintype "passive"))
      (node (ref "IC1") (pin "1") (pinfunction "OUT_1") (pintype "output"))
      (node (ref "R3") (pin "1") (pinfunction "R1_1") (pintype "passive"))
    )
    (net (code "24") (name "Net-(C2-C2)") (class "Default")
      (node (ref "C2") (pin "2") (pinfunction "C2_2") (pintype "passive"))
      (node (ref "IC1") (pin "3") (pinfunction "IN+_3") (pintype "input"))
      (node (ref "R1") (pin "1") (pinfunction "R1_1") (pintype "passive"))
    )
    (net (code "25") (name "Net-(C3-C1)") (class "Default")
      (node (ref "C3") (pin "1") (pinfunction "C1_1") (pintype "passive"))
      (node (ref "R5") (pin "1") (pinfunction "R1_1") (pintype "passive"))
    )
    (net (code "26") (name "Net-(C3-C2)") (class "Default")
      (node (ref "C3") (pin "2") (pinfunction "C2_2") (pintype "passive"))
      (node (ref "D1") (pin "3") (pinfunction "C1A2_3") (pintype "passive"))
    )
    (net (code "27") (name "Net-(C4-C2)") (class "Default")
      (node (ref "C4") (pin "2") (pinfunction "C2_2") (pintype "passive"))
      (node (ref "R9") (pin "2") (pinfunction "R2_2") (pintype "passive"))
    )
    (net (code "28") (name "Net-(C8-C1)") (class "Default")
      (node (ref "C8") (pin "2") (pinfunction "C1_2") (pintype "passive"))
      (node (ref "U1") (pin "6") (pinfunction "PH1-OSC_OUT_6") (pintype "output"))
      (node (ref "XTAL1") (pin "3") (pinfunction "3_3") (pintype "passive"))
    )
    (net (code "29") (name "Net-(C9-C1)") (class "Default")
      (node (ref "C9") (pin "2") (pinfunction "C1_2") (pintype "passive"))
      (node (ref "U1") (pin "5") (pinfunction "PH0-OSC_IN_5") (pintype "input"))
      (node (ref "XTAL1") (pin "1") (pinfunction "1_1") (pintype "passive"))
    )
    (net (code "30") (name "Net-(C16-C1)") (class "Default")
      (node (ref "C16") (pin "2") (pinfunction "C1_2") (pintype "passive"))
      (node (ref "L4") (pin "2") (pinfunction "2_2") (pintype "passive"))
    )
    (net (code "31") (name "Net-(C16-C2)") (class "Default")
      (node (ref "C16") (pin "1") (pinfunction "C2_1") (pintype "passive"))
      (node (ref "C17") (pin "1") (pinfunction "C2_1") (pintype "passive"))
      (node (ref "U$7") (pin "RF") (pinfunction "RF_RF") (pintype "bidirectional"))
    )
    (net (code "32") (name "Net-(C18-C1)") (class "Default")
      (node (ref "C18") (pin "2") (pinfunction "C1_2") (pintype "passive"))
      (node (ref "U2") (pin "10") (pinfunction "XC1_10") (pintype "input"))
      (node (ref "XTAL2") (pin "3") (pinfunction "3_3") (pintype "passive"))
    )
    (net (code "33") (name "Net-(C19-C1)") (class "Default")
      (node (ref "C19") (pin "2") (pinfunction "C1_2") (pintype "passive"))
      (node (ref "U2") (pin "9") (pinfunction "XC2_9") (pintype "input"))
      (node (ref "XTAL2") (pin "1") (pinfunction "1_1") (pintype "passive"))
    )
    (net (code "34") (name "Net-(C20-C2)") (class "Default")
      (node (ref "C20") (pin "2") (pinfunction "C2_2") (pintype "passive"))
      (node (ref "U2") (pin "19") (pinfunction "DVDD_19") (pintype "power_in"))
    )
    (net (code "35") (name "Net-(C22-C1)") (class "Default")
      (node (ref "C22") (pin "2") (pinfunction "C1_2") (pintype "passive"))
      (node (ref "L2") (pin "2") (pinfunction "2_2") (pintype "passive"))
    )
    (net (code "36") (name "Net-(C23-C2)") (class "Default")
      (node (ref "C23") (pin "2") (pinfunction "C2_2") (pintype "passive"))
      (node (ref "C24") (pin "1") (pinfunction "C2_1") (pintype "passive"))
      (node (ref "L5") (pin "2") (pinfunction "2_2") (pintype "passive"))
      (node (ref "U2") (pin "11") (pinfunction "VDD_PA_11") (pintype "power_in"))
    )
    (net (code "37") (name "Net-(C27-C1)") (class "Default")
      (node (ref "C27") (pin "1") (pinfunction "C1_1") (pintype "passive"))
      (node (ref "J3") (pin "D-") (pinfunction "D-_D-") (pintype "bidirectional"))
      (node (ref "R16") (pin "2") (pinfunction "R2_2") (pintype "passive"))
    )
    (net (code "38") (name "Net-(C28-C2)") (class "Default")
      (node (ref "C28") (pin "2") (pinfunction "C2_2") (pintype "passive"))
      (node (ref "J3") (pin "D+") (pinfunction "D+_D+") (pintype "bidirectional"))
      (node (ref "R15") (pin "1") (pinfunction "R1_1") (pintype "passive"))
      (node (ref "R17") (pin "2") (pinfunction "R2_2") (pintype "passive"))
    )
    (net (code "39") (name "Net-(C29-C1)") (class "Default")
      (node (ref "C29") (pin "2") (pinfunction "C1_2") (pintype "passive"))
      (node (ref "U3") (pin "10") (pinfunction "XC1_10") (pintype "input"))
      (node (ref "XTAL3") (pin "3") (pinfunction "3_3") (pintype "passive"))
    )
    (net (code "40") (name "Net-(C30-C1)") (class "Default")
      (node (ref "C30") (pin "2") (pinfunction "C1_2") (pintype "passive"))
      (node (ref "U3") (pin "9") (pinfunction "XC2_9") (pintype "input"))
      (node (ref "XTAL3") (pin "1") (pinfunction "1_1") (pintype "passive"))
    )
    (net (code "41") (name "Net-(C31-C2)") (class "Default")
      (node (ref "C31") (pin "2") (pinfunction "C2_2") (pintype "passive"))
      (node (ref "U3") (pin "19") (pinfunction "DVDD_19") (pintype "power_in"))
    )
    (net (code "42") (name "Net-(C33-C2)") (class "Default")
      (node (ref "C33") (pin "2") (pinfunction "C2_2") (pintype "passive"))
      (node (ref "C34") (pin "1") (pinfunction "C2_1") (pintype "passive"))
      (node (ref "L1") (pin "2") (pinfunction "2_2") (pintype "passive"))
      (node (ref "U3") (pin "11") (pinfunction "VDD_PA_11") (pintype "power_in"))
    )
    (net (code "43") (name "Net-(C35-C2)") (class "Default")
      (node (ref "C35") (pin "2") (pinfunction "C2_2") (pintype "passive"))
      (node (ref "D2") (pin "+") (pinfunction "+_+") (pintype "passive"))
      (node (ref "J3") (pin "VBUS") (pinfunction "VBUS_VBUS") (pintype "bidirectional"))
      (node (ref "U$3") (pin "4") (pinfunction "VDD_4") (pintype "power_in"))
    )
    (net (code "44") (name "Net-(D1-A1)") (class "Default")
      (node (ref "D1") (pin "1") (pinfunction "A1_1") (pintype "passive"))
      (node (ref "R6") (pin "1") (pinfunction "R1_1") (pintype "passive"))
    )
    (net (code "45") (name "Net-(IC1A-IN-)") (class "Default")
      (node (ref "IC1") (pin "2") (pinfunction "IN-_2") (pintype "input"))
      (node (ref "R3") (pin "2") (pinfunction "R2_2") (pintype "passive"))
      (node (ref "R4") (pin "1") (pinfunction "R1_1") (pintype "passive"))
    )
    (net (code "46") (name "Net-(IC1B-IN+)") (class "Default")
      (node (ref "IC1") (pin "5") (pinfunction "IN+_5") (pintype "input"))
      (node (ref "R8") (pin "1") (pinfunction "R1_1") (pintype "passive"))
      (node (ref "R9") (pin "1") (pinfunction "R1_1") (pintype "passive"))
    )
    (net (code "47") (name "Net-(R10-R1)") (class "Default")
      (node (ref "R10") (pin "1") (pinfunction "R1_1") (pintype "passive"))
      (node (ref "U$1") (pin "2") (pinfunction "EN_2") (pintype "bidirectional"))
    )
    (net (code "48") (name "Net-(R11-R1)") (class "Default")
      (node (ref "R11") (pin "1") (pinfunction "R1_1") (pintype "passive"))
      (node (ref "U3") (pin "16") (pinfunction "IREF_16") (pintype "input"))
    )
    (net (code "49") (name "Net-(R12-R1)") (class "Default")
      (node (ref "R12") (pin "1") (pinfunction "R1_1") (pintype "passive"))
      (node (ref "U$2") (pin "1") (pinfunction "COM_1") (pintype "bidirectional"))
    )
    (net (code "50") (name "Net-(R13-R1)") (class "Default")
      (node (ref "J1") (pin "1") (pinfunction "1_1") (pintype "passive"))
      (node (ref "R13") (pin "1") (pinfunction "R1_1") (pintype "passive"))
      (node (ref "U1") (pin "44") (pinfunction "BOOT0_44") (pintype "input"))
    )
    (net (code "51") (name "Net-(R14-R1)") (class "Default")
      (node (ref "R14") (pin "1") (pinfunction "R1_1") (pintype "passive"))
      (node (ref "U2") (pin "16") (pinfunction "IREF_16") (pintype "input"))
    )
    (net (code "52") (name "Net-(R18-R1)") (class "Default")
      (node (ref "R18") (pin "1") (pinfunction "R1_1") (pintype "passive"))
      (node (ref "U$3") (pin "5") (pinfunction "PROG_5") (pintype "input"))
    )
    (net (code "53") (name "Net-(R19-R1)") (class "Default")
      (node (ref "D2") (pin "-") (pinfunction "-_-") (pintype "passive"))
      (node (ref "R19") (pin "1") (pinfunction "R1_1") (pintype "passive"))
    )
    (net (code "54") (name "Net-(R19-R2)") (class "Default")
      (node (ref "R19") (pin "2") (pinfunction "R2_2") (pintype "passive"))
      (node (ref "U$3") (pin "1") (pinfunction "STAT_1") (pintype "output"))
    )
    (net (code "55") (name "Net-(U$2-B)") (class "Default")
      (node (ref "U$2") (pin "3") (pinfunction "B_3") (pintype "bidirectional"))
      (node (ref "U1") (pin "13") (pinfunction "PA3_13") (pintype "bidirectional"))
    )
    (net (code "56") (name "Net-(U$2-G)") (class "Default")
      (node (ref "U$2") (pin "4") (pinfunction "G_4") (pintype "bidirectional"))
      (node (ref "U1") (pin "11") (pinfunction "PA1_11") (pintype "bidirectional"))
    )
    (net (code "57") (name "Net-(U$2-R)") (class "Default")
      (node (ref "U$2") (pin "2") (pinfunction "R_2") (pintype "bidirectional"))
      (node (ref "U1") (pin "12") (pinfunction "PA2_12") (pintype "bidirectional"))
    )
    (net (code "58") (name "Net-(U2-ANT1)") (class "Default")
      (node (ref "L5") (pin "1") (pinfunction "1_1") (pintype "passive"))
      (node (ref "L6") (pin "1") (pinfunction "1_1") (pintype "passive"))
      (node (ref "U2") (pin "12") (pinfunction "ANT1_12") (pintype "output"))
    )
    (net (code "59") (name "Net-(U2-ANT2)") (class "Default")
      (node (ref "L4") (pin "1") (pinfunction "1_1") (pintype "passive"))
      (node (ref "L6") (pin "2") (pinfunction "2_2") (pintype "passive"))
      (node (ref "U2") (pin "13") (pinfunction "ANT2_13") (pintype "output"))
    )
    (net (code "60") (name "Net-(U3-ANT1)") (class "Default")
      (node (ref "L1") (pin "1") (pinfunction "1_1") (pintype "passive"))
      (node (ref "L3") (pin "1") (pinfunction "1_1") (pintype "passive"))
      (node (ref "U3") (pin "12") (pinfunction "ANT1_12") (pintype "output"))
    )
    (net (code "61") (name "Net-(U3-ANT2)") (class "Default")
      (node (ref "L2") (pin "1") (pinfunction "1_1") (pintype "passive"))
      (node (ref "L3") (pin "2") (pinfunction "2_2") (pintype "passive"))
      (node (ref "U3") (pin "13") (pinfunction "ANT2_13") (pintype "output"))
    )
    (net (code "62") (name "V-") (class "Default")
      (node (ref "C5") (pin "2") (pinfunction "C2_2") (pintype "passive"))
      (node (ref "C7") (pin "2") (pinfunction "C2_2") (pintype "passive"))
      (node (ref "IC1") (pin "4") (pinfunction "VCC-_4") (pintype "power_in"))
      (node (ref "R6") (pin "2") (pinfunction "R2_2") (pintype "passive"))
      (node (ref "R7") (pin "1") (pinfunction "R1_1") (pintype "passive"))
    )
    (net (code "63") (name "VCC") (class "Default")
      (node (ref "C11") (pin "2") (pinfunction "C2_2") (pintype "passive"))
      (node (ref "C12") (pin "2") (pinfunction "C2_2") (pintype "passive"))
      (node (ref "C13") (pin "2") (pinfunction "C2_2") (pintype "passive"))
      (node (ref "C14") (pin "2") (pinfunction "C2_2") (pintype "passive"))
      (node (ref "C15") (pin "2") (pinfunction "C2_2") (pintype "passive"))
      (node (ref "C21") (pin "1") (pinfunction "C2_1") (pintype "passive"))
      (node (ref "C25") (pin "2") (pinfunction "C2_2") (pintype "passive"))
      (node (ref "C32") (pin "1") (pinfunction "C2_1") (pintype "passive"))
      (node (ref "C6") (pin "2") (pinfunction "C2_2") (pintype "passive"))
      (node (ref "IC1") (pin "8") (pinfunction "VCC+_8") (pintype "power_in"))
      (node (ref "J1") (pin "2") (pinfunction "2_2") (pintype "passive"))
      (node (ref "R12") (pin "2") (pinfunction "R2_2") (pintype "passive"))
      (node (ref "R15") (pin "2") (pinfunction "R2_2") (pintype "passive"))
      (node (ref "U$1") (pin "4") (pinfunction "OUT_4") (pintype "bidirectional"))
      (node (ref "U1") (pin "24") (pinfunction "VDD_1_24") (pintype "power_in"))
      (node (ref "U1") (pin "36") (pinfunction "VDD_2_36") (pintype "power_in"))
      (node (ref "U1") (pin "48") (pinfunction "VDD_3_48") (pintype "power_in"))
      (node (ref "U1") (pin "9") (pinfunction "VDDA_9") (pintype "power_in"))
      (node (ref "U2") (pin "15") (pinfunction "VDD_15") (pintype "power_in"))
      (node (ref "U2") (pin "18") (pinfunction "VDD_18") (pintype "power_in"))
      (node (ref "U2") (pin "7") (pinfunction "VDD_7") (pintype "power_in"))
      (node (ref "U3") (pin "15") (pinfunction "VDD_15") (pintype "power_in"))
      (node (ref "U3") (pin "18") (pinfunction "VDD_18") (pintype "power_in"))
      (node (ref "U3") (pin "7") (pinfunction "VDD_7") (pintype "power_in"))
      (node (ref "U4") (pin "12") (pinfunction "3V3_12") (pintype "bidirectional"))
    )
    (net (code "64") (name "unconnected-(J3-PadID)") (class "Default")
      (node (ref "J3") (pin "ID") (pinfunction "ID_ID") (pintype "bidirectional"))
    )
    (net (code "65") (name "unconnected-(J3-PadP1)") (class "Default")
      (node (ref "J3") (pin "P1") (pinfunction "P1_P1") (pintype "bidirectional"))
    )
    (net (code "66") (name "unconnected-(J3-PadP2)") (class "Default")
      (node (ref "J3") (pin "P2") (pinfunction "P2_P2") (pintype "bidirectional"))
    )
    (net (code "67") (name "unconnected-(J3-PadP3)") (class "Default")
      (node (ref "J3") (pin "P3") (pinfunction "P3_P3") (pintype "bidirectional"))
    )
    (net (code "68") (name "unconnected-(J3-PadP4)") (class "Default")
      (node (ref "J3") (pin "P4") (pinfunction "P4_P4") (pintype "bidirectional"))
    )
    (net (code "69") (name "unconnected-(J3-PadP5)") (class "Default")
      (node (ref "J3") (pin "P5") (pinfunction "P5_P5") (pintype "bidirectional"))
    )
    (net (code "70") (name "unconnected-(J3-PadP6)") (class "Default")
      (node (ref "J3") (pin "P6") (pinfunction "P6_P6") (pintype "bidirectional"))
    )
    (net (code "71") (name "unconnected-(U1-NRST-Pad7)") (class "Default")
      (node (ref "U1") (pin "7") (pinfunction "NRST_7") (pintype "bidirectional"))
    )
    (net (code "72") (name "unconnected-(U1-P-C13_RTC_AF1-WKUP2-Pad2)") (class "Default")
      (node (ref "U1") (pin "2") (pinfunction "P-C13_RTC_AF1-WKUP2_2") (pintype "bidirectional"))
    )
    (net (code "73") (name "unconnected-(U1-PA0-WKUP1-Pad10)") (class "Default")
      (node (ref "U1") (pin "10") (pinfunction "PA0-WKUP1_10") (pintype "bidirectional"))
    )
    (net (code "74") (name "unconnected-(U1-PA5-Pad15)") (class "Default")
      (node (ref "U1") (pin "15") (pinfunction "PA5_15") (pintype "bidirectional"))
    )
    (net (code "75") (name "unconnected-(U1-PA8-Pad29)") (class "Default")
      (node (ref "U1") (pin "29") (pinfunction "PA8_29") (pintype "bidirectional"))
    )
    (net (code "76") (name "unconnected-(U1-PA13-Pad34)") (class "Default")
      (node (ref "U1") (pin "34") (pinfunction "PA13_34") (pintype "bidirectional"))
    )
    (net (code "77") (name "unconnected-(U1-PA14-Pad37)") (class "Default")
      (node (ref "U1") (pin "37") (pinfunction "PA14_37") (pintype "bidirectional"))
    )
    (net (code "78") (name "unconnected-(U1-PA15-Pad38)") (class "Default")
      (node (ref "U1") (pin "38") (pinfunction "PA15_38") (pintype "bidirectional"))
    )
    (net (code "79") (name "unconnected-(U1-PB1-Pad19)") (class "Default")
      (node (ref "U1") (pin "19") (pinfunction "PB1_19") (pintype "bidirectional"))
    )
    (net (code "80") (name "unconnected-(U1-PB2-Pad20)") (class "Default")
      (node (ref "U1") (pin "20") (pinfunction "PB2_20") (pintype "bidirectional"))
    )
    (net (code "81") (name "unconnected-(U1-PB3-Pad39)") (class "Default")
      (node (ref "U1") (pin "39") (pinfunction "PB3_39") (pintype "bidirectional"))
    )
    (net (code "82") (name "unconnected-(U1-PB4-Pad40)") (class "Default")
      (node (ref "U1") (pin "40") (pinfunction "PB4_40") (pintype "bidirectional"))
    )
    (net (code "83") (name "unconnected-(U1-PB7-Pad43)") (class "Default")
      (node (ref "U1") (pin "43") (pinfunction "PB7_43") (pintype "bidirectional"))
    )
    (net (code "84") (name "unconnected-(U1-PB8-Pad45)") (class "Default")
      (node (ref "U1") (pin "45") (pinfunction "PB8_45") (pintype "bidirectional"))
    )
    (net (code "85") (name "unconnected-(U1-PB9-Pad46)") (class "Default")
      (node (ref "U1") (pin "46") (pinfunction "PB9_46") (pintype "bidirectional"))
    )
    (net (code "86") (name "unconnected-(U1-PB12-Pad25)") (class "Default")
      (node (ref "U1") (pin "25") (pinfunction "PB12_25") (pintype "bidirectional"))
    )
    (net (code "87") (name "unconnected-(U1-PC14-OSC32_IN-Pad3)") (class "Default")
      (node (ref "U1") (pin "3") (pinfunction "PC14-OSC32_IN_3") (pintype "input"))
    )
    (net (code "88") (name "unconnected-(U1-PC15-OSC32_OUT-Pad4)") (class "Default")
      (node (ref "U1") (pin "4") (pinfunction "PC15-OSC32_OUT_4") (pintype "output"))
    )
    (net (code "89") (name "unconnected-(U2-IRQ-Pad6)") (class "Default")
      (node (ref "U2") (pin "6") (pinfunction "IRQ_6") (pintype "output"))
    )
    (net (code "90") (name "unconnected-(U3-IRQ-Pad6)") (class "Default")
      (node (ref "U3") (pin "6") (pinfunction "IRQ_6") (pintype "output"))
    )
    (net (code "91") (name "unconnected-(U4-AIO0-Pad9)") (class "Default")
      (node (ref "U4") (pin "9") (pinfunction "AIO0_9") (pintype "bidirectional"))
    )
    (net (code "92") (name "unconnected-(U4-AIO1-Pad10)") (class "Default")
      (node (ref "U4") (pin "10") (pinfunction "AIO1_10") (pintype "bidirectional"))
    )
    (net (code "93") (name "unconnected-(U4-CLK-Pad19)") (class "Default")
      (node (ref "U4") (pin "19") (pinfunction "CLK_19") (pintype "bidirectional"))
    )
    (net (code "94") (name "unconnected-(U4-CSB-Pad16)") (class "Default")
      (node (ref "U4") (pin "16") (pinfunction "CSB_16") (pintype "bidirectional"))
    )
    (net (code "95") (name "unconnected-(U4-CTS-Pad3)") (class "Default")
      (node (ref "U4") (pin "3") (pinfunction "CTS_3") (pintype "bidirectional"))
    )
    (net (code "96") (name "unconnected-(U4-GND1-Pad21)") (class "Default")
      (node (ref "U4") (pin "21") (pinfunction "GND1_21") (pintype "bidirectional"))
    )
    (net (code "97") (name "unconnected-(U4-GND2-Pad22)") (class "Default")
      (node (ref "U4") (pin "22") (pinfunction "GND2_22") (pintype "bidirectional"))
    )
    (net (code "98") (name "unconnected-(U4-MISO-Pad18)") (class "Default")
      (node (ref "U4") (pin "18") (pinfunction "MISO_18") (pintype "bidirectional"))
    )
    (net (code "99") (name "unconnected-(U4-MOSI-Pad17)") (class "Default")
      (node (ref "U4") (pin "17") (pinfunction "MOSI_17") (pintype "bidirectional"))
    )
    (net (code "100") (name "unconnected-(U4-NC-Pad14)") (class "Default")
      (node (ref "U4") (pin "14") (pinfunction "NC_14") (pintype "bidirectional"))
    )
    (net (code "101") (name "unconnected-(U4-PCM_CLK-Pad5)") (class "Default")
      (node (ref "U4") (pin "5") (pinfunction "PCM_CLK_5") (pintype "bidirectional"))
    )
    (net (code "102") (name "unconnected-(U4-PCM_IN-Pad7)") (class "Default")
      (node (ref "U4") (pin "7") (pinfunction "PCM_IN_7") (pintype "bidirectional"))
    )
    (net (code "103") (name "unconnected-(U4-PCM_OUT-Pad6)") (class "Default")
      (node (ref "U4") (pin "6") (pinfunction "PCM_OUT_6") (pintype "bidirectional"))
    )
    (net (code "104") (name "unconnected-(U4-PCN_SYNC-Pad8)") (class "Default")
      (node (ref "U4") (pin "8") (pinfunction "PCN_SYNC_8") (pintype "bidirectional"))
    )
    (net (code "105") (name "unconnected-(U4-PIO0-Pad23)") (class "Default")
      (node (ref "U4") (pin "23") (pinfunction "PIO0_23") (pintype "bidirectional"))
    )
    (net (code "106") (name "unconnected-(U4-PIO2-Pad25)") (class "Default")
      (node (ref "U4") (pin "25") (pinfunction "PIO2_25") (pintype "bidirectional"))
    )
    (net (code "107") (name "unconnected-(U4-PIO4-Pad27)") (class "Default")
      (node (ref "U4") (pin "27") (pinfunction "PIO4_27") (pintype "bidirectional"))
    )
    (net (code "108") (name "unconnected-(U4-PIO5-Pad28)") (class "Default")
      (node (ref "U4") (pin "28") (pinfunction "PIO5_28") (pintype "bidirectional"))
    )
    (net (code "109") (name "unconnected-(U4-PIO6-Pad29)") (class "Default")
      (node (ref "U4") (pin "29") (pinfunction "PIO6_29") (pintype "bidirectional"))
    )
    (net (code "110") (name "unconnected-(U4-PIO7-Pad30)") (class "Default")
      (node (ref "U4") (pin "30") (pinfunction "PIO7_30") (pintype "bidirectional"))
    )
    (net (code "111") (name "unconnected-(U4-PIO8-Pad31)") (class "Default")
      (node (ref "U4") (pin "31") (pinfunction "PIO8_31") (pintype "bidirectional"))
    )
    (net (code "112") (name "unconnected-(U4-PIO9-Pad32)") (class "Default")
      (node (ref "U4") (pin "32") (pinfunction "PIO9_32") (pintype "bidirectional"))
    )
    (net (code "113") (name "unconnected-(U4-PIO10-Pad33)") (class "Default")
      (node (ref "U4") (pin "33") (pinfunction "PIO10_33") (pintype "bidirectional"))
    )
    (net (code "114") (name "unconnected-(U4-PIO11-Pad34)") (class "Default")
      (node (ref "U4") (pin "34") (pinfunction "PIO11_34") (pintype "bidirectional"))
    )
    (net (code "115") (name "unconnected-(U4-RST-Pad11)") (class "Default")
      (node (ref "U4") (pin "11") (pinfunction "RST_11") (pintype "bidirectional"))
    )
    (net (code "116") (name "unconnected-(U4-RTS-Pad4)") (class "Default")
      (node (ref "U4") (pin "4") (pinfunction "RTS_4") (pintype "bidirectional"))
    )
    (net (code "117") (name "unconnected-(U4-VBUSD+-Pad20)") (class "Default")
      (node (ref "U4") (pin "20") (pinfunction "VBUSD+_20") (pintype "bidirectional"))
    )
    (net (code "118") (name "unconnected-(U4-VBUSD--Pad15)") (class "Default")
      (node (ref "U4") (pin "15") (pinfunction "VBUSD-_15") (pintype "bidirectional"))
    )
  )
)
